# analog_inputs.net
KiCad netlist of a schematic drawn in EAGLE
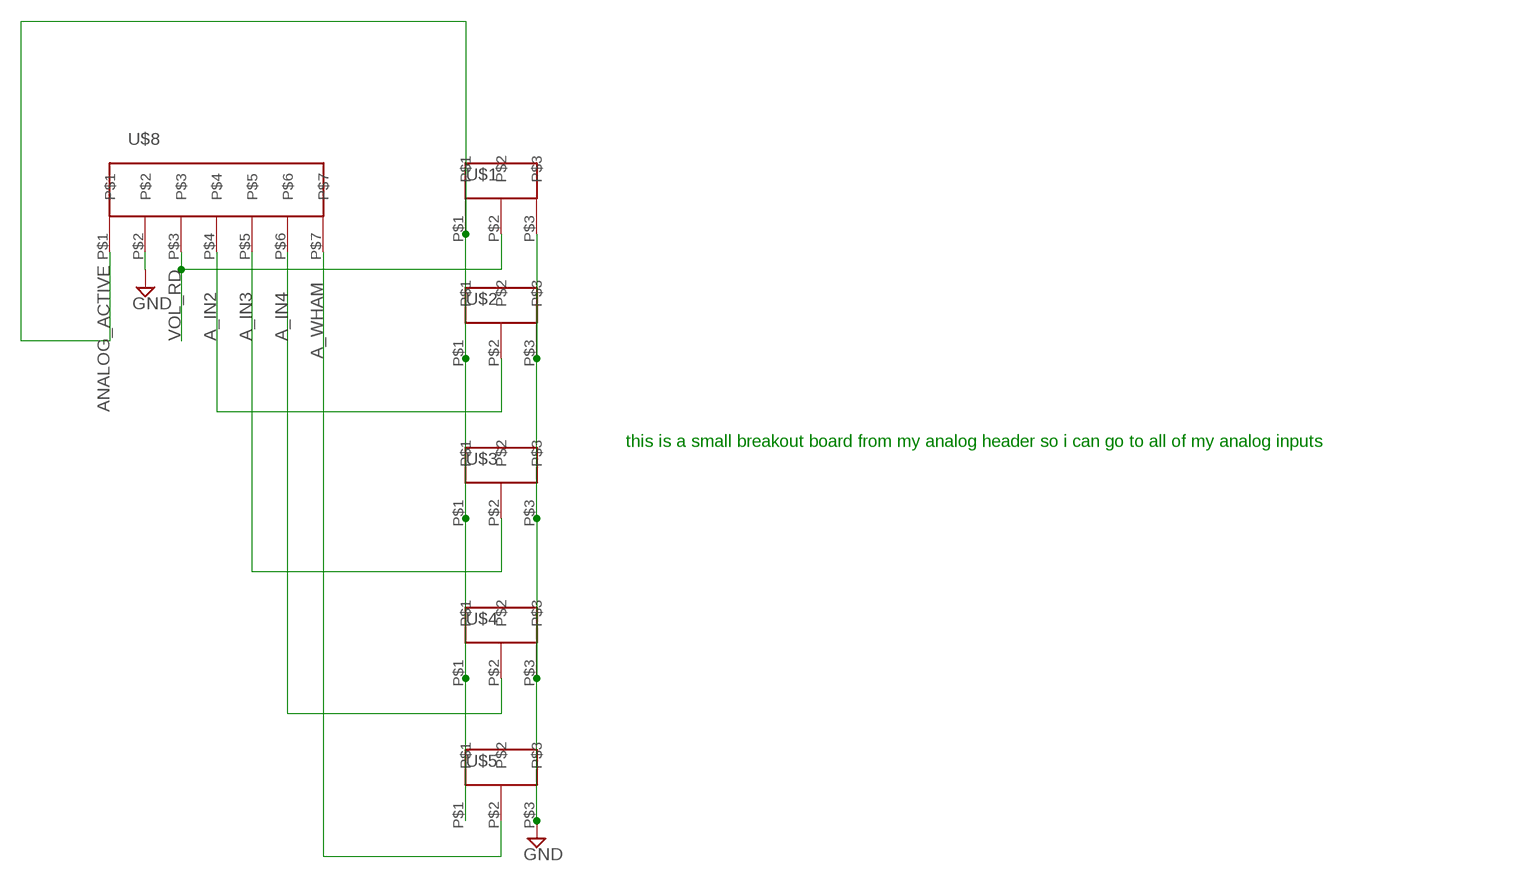
[diagram p0: schematic, sheet 1]

(export (version "E")
  (design (tool "Eeschema 10.0.6"))
  (components
    (comp (ref "U$1")
      (value "3-PIN-HEADER")
      (footprint "eagle-import:3-PIN-HEADER")
      (libsource (lib "eagle-import") (part "3-PIN-HEADER"))
    )
    (comp (ref "U$2")
      (value "3-PIN-HEADER")
      (footprint "eagle-import:3-PIN-HEADER")
      (libsource (lib "eagle-import") (part "3-PIN-HEADER"))
    )
    (comp (ref "U$3")
      (value "3-PIN-HEADER")
      (footprint "eagle-import:3-PIN-HEADER")
      (libsource (lib "eagle-import") (part "3-PIN-HEADER"))
    )
    (comp (ref "U$4")
      (value "3-PIN-HEADER")
      (footprint "eagle-import:3-PIN-HEADER")
      (libsource (lib "eagle-import") (part "3-PIN-HEADER"))
    )
    (comp (ref "U$5")
      (value "3-PIN-HEADER")
      (footprint "eagle-import:3-PIN-HEADER")
      (libsource (lib "eagle-import") (part "3-PIN-HEADER"))
    )
    (comp (ref "U$8")
      (value "7-PIN-HEADER")
      (footprint "eagle-import:7-PIN-HEADER")
      (libsource (lib "eagle-import") (part "7-PIN-HEADER"))
    )
  )
  (nets
    (net (code "1") (name "/ANALOG_ACTIVE") (class "Default")
      (node (ref "U$1") (pin "P$1") (pinfunction "P$1_P$1") (pintype "bidirectional"))
      (node (ref "U$2") (pin "P$1") (pinfunction "P$1_P$1") (pintype "bidirectional"))
      (node (ref "U$3") (pin "P$1") (pinfunction "P$1_P$1") (pintype "bidirectional"))
      (node (ref "U$4") (pin "P$1") (pinfunction "P$1_P$1") (pintype "bidirectional"))
      (node (ref "U$5") (pin "P$1") (pinfunction "P$1_P$1") (pintype "bidirectional"))
      (node (ref "U$8") (pin "P$1") (pinfunction "P$1_P$1") (pintype "bidirectional"))
    )
    (net (code "2") (name "/A_IN2") (class "Default")
      (node (ref "U$2") (pin "P$2") (pinfunction "P$2_P$2") (pintype "bidirectional"))
      (node (ref "U$8") (pin "P$4") (pinfunction "P$4_P$4") (pintype "bidirectional"))
    )
    (net (code "3") (name "/A_IN3") (class "Default")
      (node (ref "U$3") (pin "P$2") (pinfunction "P$2_P$2") (pintype "bidirectional"))
      (node (ref "U$8") (pin "P$5") (pinfunction "P$5_P$5") (pintype "bidirectional"))
    )
    (net (code "4") (name "/A_IN4") (class "Default")
      (node (ref "U$4") (pin "P$2") (pinfunction "P$2_P$2") (pintype "bidirectional"))
      (node (ref "U$8") (pin "P$6") (pinfunction "P$6_P$6") (pintype "bidirectional"))
    )
    (net (code "5") (name "/A_WHAM") (class "Default")
      (node (ref "U$5") (pin "P$2") (pinfunction "P$2_P$2") (pintype "bidirectional"))
      (node (ref "U$8") (pin "P$7") (pinfunction "P$7_P$7") (pintype "bidirectional"))
    )
    (net (code "6") (name "/VOL_RD") (class "Default")
      (node (ref "U$1") (pin "P$2") (pinfunction "P$2_P$2") (pintype "bidirectional"))
      (node (ref "U$8") (pin "P$3") (pinfunction "P$3_P$3") (pintype "bidirectional"))
    )
    (net (code "7") (name "GND") (class "Default")
      (node (ref "U$1") (pin "P$3") (pinfunction "P$3_P$3") (pintype "bidirectional"))
      (node (ref "U$2") (pin "P$3") (pinfunction "P$3_P$3") (pintype "bidirectional"))
      (node (ref "U$3") (pin "P$3") (pinfunction "P$3_P$3") (pintype "bidirectional"))
      (node (ref "U$4") (pin "P$3") (pinfunction "P$3_P$3") (pintype "bidirectional"))
      (node (ref "U$5") (pin "P$3") (pinfunction "P$3_P$3") (pintype "bidirectional"))
      (node (ref "U$8") (pin "P$2") (pinfunction "P$2_P$2") (pintype "bidirectional"))
    )
  )
)
